# top.net
KiCad netlist of a schematic drawn in EAGLE
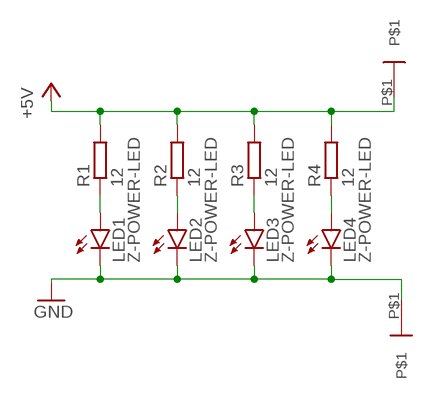
[diagram p0: schematic, sheet 1]

(export (version "E")
  (design (tool "Eeschema 10.0.6"))
  (components
    (comp (ref "LED1")
      (value "Z-POWER-LED")
      (footprint "eagle-import:Z-POWER-LED-PCB-TYPE")
      (libsource (lib "eagle-import") (part "Z-POWER-LED"))
    )
    (comp (ref "LED2")
      (value "Z-POWER-LED")
      (footprint "eagle-import:Z-POWER-LED-PCB-TYPE")
      (libsource (lib "eagle-import") (part "Z-POWER-LED"))
    )
    (comp (ref "LED3")
      (value "Z-POWER-LED")
      (footprint "eagle-import:Z-POWER-LED-PCB-TYPE")
      (libsource (lib "eagle-import") (part "Z-POWER-LED"))
    )
    (comp (ref "LED4")
      (value "Z-POWER-LED")
      (footprint "eagle-import:Z-POWER-LED-PCB-TYPE")
      (libsource (lib "eagle-import") (part "Z-POWER-LED"))
    )
    (comp (ref "R1")
      (value "12")
      (footprint "eagle-import:R0805")
      (libsource (lib "eagle-import") (part "R-EU_R0805"))
    )
    (comp (ref "R2")
      (value "12")
      (footprint "eagle-import:R0805")
      (libsource (lib "eagle-import") (part "R-EU_R0805"))
    )
    (comp (ref "R3")
      (value "12")
      (footprint "eagle-import:R0805")
      (libsource (lib "eagle-import") (part "R-EU_R0805"))
    )
    (comp (ref "R4")
      (value "12")
      (footprint "eagle-import:R0805")
      (libsource (lib "eagle-import") (part "R-EU_R0805"))
    )
    (comp (ref "U$1")
      (value "PAD")
      (footprint "eagle-import:PAD")
      (libsource (lib "eagle-import") (part "PAD"))
    )
    (comp (ref "U$2")
      (value "PAD")
      (footprint "eagle-import:PAD")
      (libsource (lib "eagle-import") (part "PAD"))
    )
  )
  (nets
    (net (code "1") (name "+5V") (class "Default")
      (node (ref "R1") (pin "2") (pinfunction "2_2") (pintype "passive"))
      (node (ref "R2") (pin "2") (pinfunction "2_2") (pintype "passive"))
      (node (ref "R3") (pin "2") (pinfunction "2_2") (pintype "passive"))
      (node (ref "R4") (pin "2") (pinfunction "2_2") (pintype "passive"))
      (node (ref "U$2") (pin "P$1") (pinfunction "P$1_P$1") (pintype "bidirectional"))
    )
    (net (code "2") (name "GND") (class "Default")
      (node (ref "LED1") (pin "C") (pinfunction "C_C") (pintype "passive"))
      (node (ref "LED2") (pin "C") (pinfunction "C_C") (pintype "passive"))
      (node (ref "LED3") (pin "C") (pinfunction "C_C") (pintype "passive"))
      (node (ref "LED4") (pin "C") (pinfunction "C_C") (pintype "passive"))
      (node (ref "U$1") (pin "P$1") (pinfunction "P$1_P$1") (pintype "bidirectional"))
    )
    (net (code "3") (name "Net-(LED1-PadA)") (class "Default")
      (node (ref "LED1") (pin "A") (pinfunction "A_A") (pintype "passive"))
      (node (ref "R1") (pin "1") (pinfunction "1_1") (pintype "passive"))
    )
    (net (code "4") (name "Net-(LED2-PadA)") (class "Default")
      (node (ref "LED2") (pin "A") (pinfunction "A_A") (pintype "passive"))
      (node (ref "R2") (pin "1") (pinfunction "1_1") (pintype "passive"))
    )
    (net (code "5") (name "Net-(LED3-PadA)") (class "Default")
      (node (ref "LED3") (pin "A") (pinfunction "A_A") (pintype "passive"))
      (node (ref "R3") (pin "1") (pinfunction "1_1") (pintype "passive"))
    )
    (net (code "6") (name "Net-(LED4-PadA)") (class "Default")
      (node (ref "LED4") (pin "A") (pinfunction "A_A") (pintype "passive"))
      (node (ref "R4") (pin "1") (pinfunction "1_1") (pintype "passive"))
    )
  )
)
